# Pg09_1G_b.net
KiCad netlist of a schematic drawn in Altium Designer
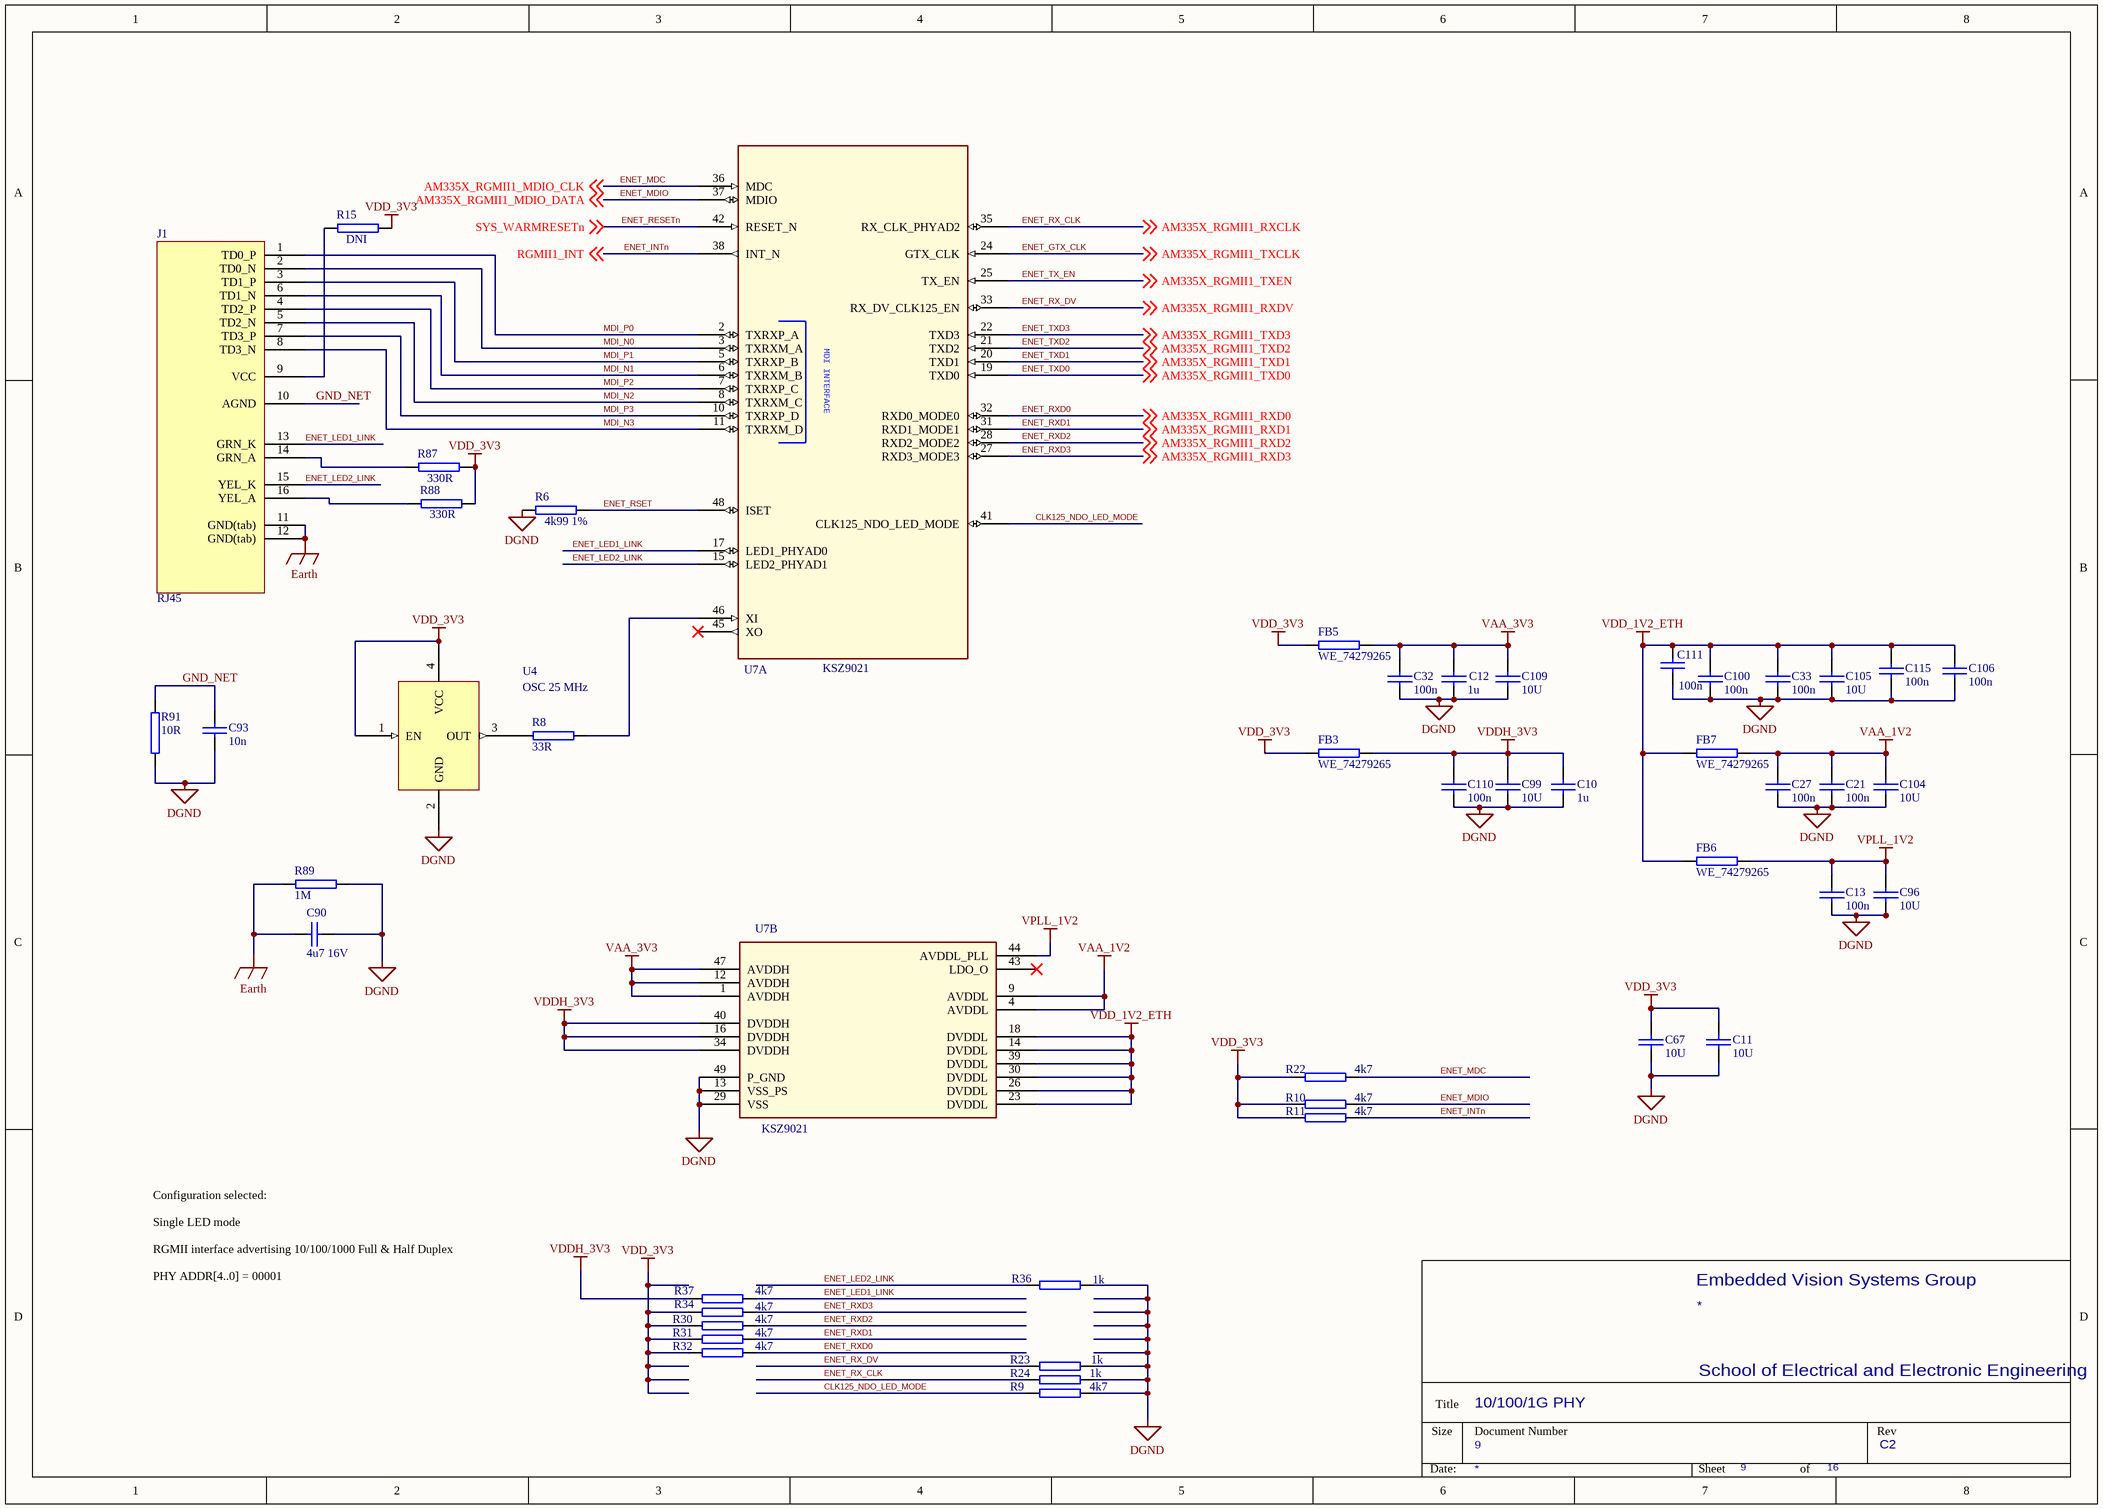
[diagram p0: Pg09_1G_b.SchDoc]

(export (version "E")
  (design (tool "Eeschema 10.0.6"))
  (components
    (comp (ref "C10")
      (value "1u")
      (footprint "0603")
      (description "NON-POLARISED CAP")
      (libsource (lib "Fireflash_B") (part "CAP"))
    )
    (comp (ref "C11")
      (value "10U")
      (footprint "0603")
      (description "NON-POLARISED CAP")
      (libsource (lib "ARMflash1_revC") (part "CAP"))
    )
    (comp (ref "C12")
      (value "1u")
      (footprint "0603")
      (description "NON-POLARISED CAP")
      (libsource (lib "ARMflash1_revC") (part "CAP"))
    )
    (comp (ref "C13")
      (value "100n")
      (footprint "SM-7351-CAP-0402")
      (description "NON-POLARISED CAP")
      (libsource (lib "ARMflash1_revC") (part "CAP"))
    )
    (comp (ref "C21")
      (value "100n")
      (footprint "SM-7351-CAP-0402")
      (description "NON-POLARISED CAP")
      (libsource (lib "ARMflash1_revC") (part "CAP"))
    )
    (comp (ref "C27")
      (value "100n")
      (footprint "SM-7351-CAP-0402")
      (description "NON-POLARISED CAP")
      (libsource (lib "ARMflash1_revC") (part "CAP"))
    )
    (comp (ref "C32")
      (value "100n")
      (footprint "0603")
      (description "NON-POLARISED CAP")
      (libsource (lib "ARMflash1_revC") (part "CAP"))
    )
    (comp (ref "C33")
      (value "100n")
      (footprint "sc0402")
      (description "NON-POLARISED CAP")
      (libsource (lib "ARMflash1_revC") (part "CAP"))
    )
    (comp (ref "C67")
      (value "10U")
      (footprint "0603")
      (description "NON-POLARISED CAP")
      (libsource (lib "ARMflash1_revC") (part "CAP"))
    )
    (comp (ref "C90")
      (value "4u7 16V")
      (footprint "0603")
      (description "NON-POLARISED CAP")
      (libsource (lib "ARMflash1_revC") (part "CAP"))
    )
    (comp (ref "C93")
      (value "10n")
      (footprint "0603")
      (description "NON-POLARISED CAP")
      (libsource (lib "ARMflash1_revC") (part "CAP"))
    )
    (comp (ref "C96")
      (value "10U")
      (footprint "0603")
      (description "NON-POLARISED CAP")
      (libsource (lib "ARMflash1_revC") (part "CAP"))
    )
    (comp (ref "C99")
      (value "10U")
      (footprint "0603")
      (description "NON-POLARISED CAP")
      (libsource (lib "ARMflash1_revC") (part "CAP"))
    )
    (comp (ref "C100")
      (value "100n")
      (footprint "SM-7351-CAP-0402")
      (description "NON-POLARISED CAP")
      (libsource (lib "ARMflash1_revC") (part "CAP"))
    )
    (comp (ref "C104")
      (value "10U")
      (footprint "0603")
      (description "NON-POLARISED CAP")
      (libsource (lib "ARMflash1_revC") (part "CAP"))
    )
    (comp (ref "C105")
      (value "10U")
      (footprint "0603")
      (description "NON-POLARISED CAP")
      (libsource (lib "ARMflash1_revC") (part "CAP"))
    )
    (comp (ref "C106")
      (value "100n")
      (footprint "0603")
      (description "NON-POLARISED CAP")
      (libsource (lib "Fireflash_B") (part "CAP"))
    )
    (comp (ref "C109")
      (value "10U")
      (footprint "0603")
      (description "NON-POLARISED CAP")
      (libsource (lib "ARMflash1_revC") (part "CAP"))
    )
    (comp (ref "C110")
      (value "100n")
      (footprint "0603")
      (description "NON-POLARISED CAP")
      (libsource (lib "ARMflash1_revC") (part "CAP"))
    )
    (comp (ref "C111")
      (value "100n")
      (footprint "0603")
      (description "NON-POLARISED CAP")
      (libsource (lib "ARMflash1_revC") (part "CAP"))
    )
    (comp (ref "C115")
      (value "100n")
      (footprint "SM-7351-CAP-0402")
      (description "NON-POLARISED CAP")
      (libsource (lib "ARMflash1_revC") (part "CAP"))
    )
    (comp (ref "FB3")
      (value "WE_74279265")
      (footprint "0603")
      (description "Wurth Eleckronik 0603 ferrite bead pn 74279265")
      (libsource (lib "Ibis4") (part "WE_74279265"))
    )
    (comp (ref "FB5")
      (value "WE_74279265")
      (footprint "0603")
      (description "Wurth Eleckronik 0603 ferrite bead pn 74279265")
      (libsource (lib "Ibis4") (part "WE_74279265"))
    )
    (comp (ref "FB6")
      (value "WE_74279265")
      (footprint "0603")
      (description "Wurth Eleckronik 0603 ferrite bead pn 74279265")
      (libsource (lib "Ibis4") (part "WE_74279265"))
    )
    (comp (ref "FB7")
      (value "WE_74279265")
      (footprint "0603")
      (description "Wurth Eleckronik 0603 ferrite bead pn 74279265")
      (libsource (lib "Ibis4") (part "WE_74279265"))
    )
    (comp (ref "J1")
      (value "RJ45")
      (footprint "RJ45_tripleSpeed")
      (description "RJ45 Mag Jack triple speed")
      (libsource (lib "ARMflash_mini_revB_rev") (part "WE_7499111121A RJ45 triple speed"))
    )
    (comp (ref "R6")
      (value "4k99 1%")
      (footprint "sc0402")
      (description "RESISTOR")
      (libsource (lib "Fireflash_B") (part "RES"))
    )
    (comp (ref "R8")
      (value "33R")
      (footprint "sc0402")
      (description "RESISTOR")
      (libsource (lib "Fireflash_B") (part "RES"))
    )
    (comp (ref "R9")
      (value "4k7")
      (footprint "sc0402")
      (description "RESISTOR")
      (libsource (lib "Fireflash_B") (part "RES"))
    )
    (comp (ref "R10")
      (value "4k7")
      (footprint "sc0402")
      (description "RESISTOR")
      (libsource (lib "Fireflash_B") (part "RES"))
    )
    (comp (ref "R11")
      (value "4k7")
      (footprint "sc0402")
      (description "RESISTOR")
      (libsource (lib "Fireflash_B") (part "RES"))
    )
    (comp (ref "R15")
      (value "DNI")
      (footprint "sc0402")
      (description "RESISTOR")
      (libsource (lib "Fireflash_B") (part "RES"))
    )
    (comp (ref "R22")
      (value "4k7")
      (footprint "sc0402")
      (description "RESISTOR")
      (libsource (lib "Fireflash_B") (part "RES"))
    )
    (comp (ref "R23")
      (value "1k")
      (footprint "sc0402")
      (description "RESISTOR")
      (libsource (lib "Fireflash_B") (part "RES"))
    )
    (comp (ref "R24")
      (value "1k")
      (footprint "sc0402")
      (description "RESISTOR")
      (libsource (lib "Fireflash_B") (part "RES"))
    )
    (comp (ref "R30")
      (value "4k7")
      (footprint "sc0402")
      (description "RESISTOR")
      (libsource (lib "Fireflash_B") (part "RES"))
    )
    (comp (ref "R31")
      (value "4k7")
      (footprint "sc0402")
      (description "RESISTOR")
      (libsource (lib "Fireflash_B") (part "RES"))
    )
    (comp (ref "R32")
      (value "4k7")
      (footprint "sc0402")
      (description "RESISTOR")
      (libsource (lib "Fireflash_B") (part "RES"))
    )
    (comp (ref "R34")
      (value "4k7")
      (footprint "sc0402")
      (description "RESISTOR")
      (libsource (lib "Fireflash_B") (part "RES"))
    )
    (comp (ref "R36")
      (value "1k")
      (footprint "sc0402")
      (description "RESISTOR")
      (libsource (lib "Fireflash_B") (part "RES"))
    )
    (comp (ref "R37")
      (value "4k7")
      (footprint "sc0402")
      (description "RESISTOR")
      (libsource (lib "Fireflash_B") (part "RES"))
    )
    (comp (ref "R87")
      (value "330R")
      (footprint "sc0402")
      (description "RESISTOR")
      (libsource (lib "Fireflash_B") (part "RES"))
    )
    (comp (ref "R88")
      (value "330R")
      (footprint "sc0402")
      (description "RESISTOR")
      (libsource (lib "Fireflash_B") (part "RES"))
    )
    (comp (ref "R89")
      (value "1M")
      (footprint "0603")
      (description "RESISTOR")
      (libsource (lib "Fireflash_B") (part "RES"))
    )
    (comp (ref "R91")
      (value "10R")
      (footprint "0603")
      (description "RESISTOR")
      (libsource (lib "Fireflash_B") (part "RES"))
    )
    (comp (ref "U4")
      (value "OSC 25 MHz")
      (footprint "Osc 3.2x2.5")
      (description "XTAL OSCILLATOR MODULE")
      (libsource (lib "ARMflash_mini") (part "OSC"))
    )
    (comp (ref "U7")
      (value "KSZ9021")
      (footprint "QFN48_0.5mmPitch")
      (libsource (lib "*") (part "KSZ9021RN_4"))
    )
  )
  (nets
    (net (code "1") (name "/CLK125_NDO_LED_MODE") (class "Default")
      (node (ref "R9") (pin "1") (pintype "passive"))
      (node (ref "U7") (pin "41") (pinfunction "CLK125_NDO_LED_MODE_41") (pintype "bidirectional"))
    )
    (net (code "2") (name "/ENET_LED1_LINK") (class "Default")
      (node (ref "J1") (pin "13") (pinfunction "GRN_K_13") (pintype "passive"))
      (node (ref "R37") (pin "2") (pintype "passive"))
      (node (ref "U7") (pin "17") (pinfunction "LED1_PHYAD0_17") (pintype "bidirectional"))
    )
    (net (code "3") (name "/ENET_LED2_LINK") (class "Default")
      (node (ref "J1") (pin "15") (pinfunction "YEL_K_15") (pintype "passive"))
      (node (ref "R36") (pin "1") (pintype "passive"))
      (node (ref "U7") (pin "15") (pinfunction "LED2_PHYAD1_15") (pintype "bidirectional"))
    )
    (net (code "4") (name "/ENET_RSET") (class "Default")
      (node (ref "R6") (pin "2") (pintype "passive"))
      (node (ref "U7") (pin "48") (pinfunction "ISET_48") (pintype "bidirectional"))
    )
    (net (code "5") (name "/GND_NET") (class "Default")
      (node (ref "C93") (pin "1") (pintype "passive"))
      (node (ref "J1") (pin "10") (pinfunction "AGND_10") (pintype "passive"))
      (node (ref "R91") (pin "2") (pintype "passive"))
    )
    (net (code "6") (name "/MDI_N0") (class "Default")
      (node (ref "J1") (pin "2") (pinfunction "TD0_N_2") (pintype "passive"))
      (node (ref "U7") (pin "3") (pinfunction "TXRXM_A_3") (pintype "bidirectional"))
    )
    (net (code "7") (name "/MDI_N1") (class "Default")
      (node (ref "J1") (pin "6") (pinfunction "TD1_N_6") (pintype "passive"))
      (node (ref "U7") (pin "6") (pinfunction "TXRXM_B_6") (pintype "bidirectional"))
    )
    (net (code "8") (name "/MDI_N2") (class "Default")
      (node (ref "J1") (pin "5") (pinfunction "TD2_N_5") (pintype "passive"))
      (node (ref "U7") (pin "8") (pinfunction "TXRXM_C_8") (pintype "bidirectional"))
    )
    (net (code "9") (name "/MDI_N3") (class "Default")
      (node (ref "J1") (pin "8") (pinfunction "TD3_N_8") (pintype "passive"))
      (node (ref "U7") (pin "11") (pinfunction "TXRXM_D_11") (pintype "bidirectional"))
    )
    (net (code "10") (name "/MDI_P0") (class "Default")
      (node (ref "J1") (pin "1") (pinfunction "TD0_P_1") (pintype "passive"))
      (node (ref "U7") (pin "2") (pinfunction "TXRXP_A_2") (pintype "bidirectional"))
    )
    (net (code "11") (name "/MDI_P1") (class "Default")
      (node (ref "J1") (pin "3") (pinfunction "TD1_P_3") (pintype "passive"))
      (node (ref "U7") (pin "5") (pinfunction "TXRXP_B_5") (pintype "bidirectional"))
    )
    (net (code "12") (name "/MDI_P2") (class "Default")
      (node (ref "J1") (pin "4") (pinfunction "TD2_P_4") (pintype "passive"))
      (node (ref "U7") (pin "7") (pinfunction "TXRXP_C_7") (pintype "bidirectional"))
    )
    (net (code "13") (name "/MDI_P3") (class "Default")
      (node (ref "J1") (pin "7") (pinfunction "TD3_P_7") (pintype "passive"))
      (node (ref "U7") (pin "10") (pinfunction "TXRXP_D_10") (pintype "bidirectional"))
    )
    (net (code "14") (name "AM335X_RGMII1_MDIO_CLK") (class "Default")
      (node (ref "R22") (pin "2") (pintype "passive"))
      (node (ref "U7") (pin "36") (pinfunction "MDC_36") (pintype "input"))
    )
    (net (code "15") (name "AM335X_RGMII1_MDIO_DATA") (class "Default")
      (node (ref "R10") (pin "2") (pintype "passive"))
      (node (ref "U7") (pin "37") (pinfunction "MDIO_37") (pintype "bidirectional"))
    )
    (net (code "16") (name "AM335X_RGMII1_RXCLK") (class "Default")
      (node (ref "R24") (pin "1") (pintype "passive"))
      (node (ref "U7") (pin "35") (pinfunction "RX_CLK_PHYAD2_35") (pintype "bidirectional"))
    )
    (net (code "17") (name "AM335X_RGMII1_RXD0") (class "Default")
      (node (ref "R32") (pin "2") (pintype "passive"))
      (node (ref "U7") (pin "32") (pinfunction "RXD0_MODE0_32") (pintype "bidirectional"))
    )
    (net (code "18") (name "AM335X_RGMII1_RXD1") (class "Default")
      (node (ref "R31") (pin "2") (pintype "passive"))
      (node (ref "U7") (pin "31") (pinfunction "RXD1_MODE1_31") (pintype "bidirectional"))
    )
    (net (code "19") (name "AM335X_RGMII1_RXD2") (class "Default")
      (node (ref "R30") (pin "2") (pintype "passive"))
      (node (ref "U7") (pin "28") (pinfunction "RXD2_MODE2_28") (pintype "bidirectional"))
    )
    (net (code "20") (name "AM335X_RGMII1_RXD3") (class "Default")
      (node (ref "R34") (pin "2") (pintype "passive"))
      (node (ref "U7") (pin "27") (pinfunction "RXD3_MODE3_27") (pintype "bidirectional"))
    )
    (net (code "21") (name "AM335X_RGMII1_RXDV") (class "Default")
      (node (ref "R23") (pin "1") (pintype "passive"))
      (node (ref "U7") (pin "33") (pinfunction "RX_DV_CLK125_EN_33") (pintype "bidirectional"))
    )
    (net (code "22") (name "AM335X_RGMII1_TXCLK") (class "Default")
      (node (ref "U7") (pin "24") (pinfunction "GTX_CLK_24") (pintype "input"))
    )
    (net (code "23") (name "AM335X_RGMII1_TXD0") (class "Default")
      (node (ref "U7") (pin "19") (pinfunction "TXD0_19") (pintype "input"))
    )
    (net (code "24") (name "AM335X_RGMII1_TXD1") (class "Default")
      (node (ref "U7") (pin "20") (pinfunction "TXD1_20") (pintype "input"))
    )
    (net (code "25") (name "AM335X_RGMII1_TXD2") (class "Default")
      (node (ref "U7") (pin "21") (pinfunction "TXD2_21") (pintype "input"))
    )
    (net (code "26") (name "AM335X_RGMII1_TXD3") (class "Default")
      (node (ref "U7") (pin "22") (pinfunction "TXD3_22") (pintype "input"))
    )
    (net (code "27") (name "AM335X_RGMII1_TXEN") (class "Default")
      (node (ref "U7") (pin "25") (pinfunction "TX_EN_25") (pintype "input"))
    )
    (net (code "28") (name "DGND") (class "Default")
      (node (ref "C10") (pin "2") (pintype "passive"))
      (node (ref "C100") (pin "2") (pintype "passive"))
      (node (ref "C104") (pin "2") (pintype "passive"))
      (node (ref "C105") (pin "2") (pintype "passive"))
      (node (ref "C106") (pin "2") (pintype "passive"))
      (node (ref "C109") (pin "2") (pintype "passive"))
      (node (ref "C11") (pin "2") (pintype "passive"))
      (node (ref "C110") (pin "2") (pintype "passive"))
      (node (ref "C111") (pin "2") (pintype "passive"))
      (node (ref "C115") (pin "2") (pintype "passive"))
      (node (ref "C12") (pin "2") (pintype "passive"))
      (node (ref "C13") (pin "2") (pintype "passive"))
      (node (ref "C21") (pin "2") (pintype "passive"))
      (node (ref "C27") (pin "2") (pintype "passive"))
      (node (ref "C32") (pin "2") (pintype "passive"))
      (node (ref "C33") (pin "2") (pintype "passive"))
      (node (ref "C67") (pin "2") (pintype "passive"))
      (node (ref "C90") (pin "2") (pintype "passive"))
      (node (ref "C93") (pin "2") (pintype "passive"))
      (node (ref "C96") (pin "2") (pintype "passive"))
      (node (ref "C99") (pin "2") (pintype "passive"))
      (node (ref "R23") (pin "2") (pintype "passive"))
      (node (ref "R24") (pin "2") (pintype "passive"))
      (node (ref "R36") (pin "2") (pintype "passive"))
      (node (ref "R6") (pin "1") (pintype "passive"))
      (node (ref "R89") (pin "1") (pintype "passive"))
      (node (ref "R9") (pin "2") (pintype "passive"))
      (node (ref "R91") (pin "1") (pintype "passive"))
      (node (ref "U4") (pin "2") (pinfunction "GND_2") (pintype "power_in"))
      (node (ref "U7") (pin "13") (pinfunction "VSS_PS_13") (pintype "power_in"))
      (node (ref "U7") (pin "29") (pinfunction "VSS_29") (pintype "power_in"))
      (node (ref "U7") (pin "49") (pinfunction "P_GND_49") (pintype "power_in"))
    )
    (net (code "29") (name "Earth") (class "Default")
      (node (ref "C90") (pin "1") (pintype "passive"))
      (node (ref "J1") (pin "11") (pinfunction "GND(tab)_11") (pintype "passive"))
      (node (ref "J1") (pin "12") (pinfunction "GND(tab)_12") (pintype "passive"))
      (node (ref "R89") (pin "2") (pintype "passive"))
    )
    (net (code "30") (name "Net-(J1-GRN_A)") (class "Default")
      (node (ref "J1") (pin "14") (pinfunction "GRN_A_14") (pintype "passive"))
      (node (ref "R87") (pin "1") (pintype "passive"))
    )
    (net (code "31") (name "Net-(J1-VCC)") (class "Default")
      (node (ref "J1") (pin "9") (pinfunction "VCC_9") (pintype "passive"))
      (node (ref "R15") (pin "1") (pintype "passive"))
    )
    (net (code "32") (name "Net-(J1-YEL_A)") (class "Default")
      (node (ref "J1") (pin "16") (pinfunction "YEL_A_16") (pintype "passive"))
      (node (ref "R88") (pin "1") (pintype "passive"))
    )
    (net (code "33") (name "Net-(U4-OUT)") (class "Default")
      (node (ref "R8") (pin "1") (pintype "passive"))
      (node (ref "U4") (pin "3") (pinfunction "OUT_3") (pintype "output"))
    )
    (net (code "34") (name "Net-(U7A-XI)") (class "Default")
      (node (ref "R8") (pin "2") (pintype "passive"))
      (node (ref "U7") (pin "46") (pinfunction "XI_46") (pintype "input"))
    )
    (net (code "35") (name "RGMII1_INT") (class "Default")
      (node (ref "R11") (pin "2") (pintype "passive"))
      (node (ref "U7") (pin "38") (pinfunction "INT_N_38") (pintype "output"))
    )
    (net (code "36") (name "SYS_WARMRESETn") (class "Default")
      (node (ref "U7") (pin "42") (pinfunction "RESET_N_42") (pintype "input"))
    )
    (net (code "37") (name "VAA_1V2") (class "Default")
      (node (ref "C104") (pin "1") (pintype "passive"))
      (node (ref "C21") (pin "1") (pintype "passive"))
      (node (ref "C27") (pin "1") (pintype "passive"))
      (node (ref "FB7") (pin "2") (pintype "passive"))
      (node (ref "U7") (pin "4") (pinfunction "AVDDL_4") (pintype "power_in"))
      (node (ref "U7") (pin "9") (pinfunction "AVDDL_9") (pintype "power_in"))
    )
    (net (code "38") (name "VAA_3V3") (class "Default")
      (node (ref "C109") (pin "1") (pintype "passive"))
      (node (ref "C12") (pin "1") (pintype "passive"))
      (node (ref "C32") (pin "1") (pintype "passive"))
      (node (ref "FB5") (pin "2") (pintype "passive"))
      (node (ref "U7") (pin "1") (pinfunction "AVDDH_1") (pintype "power_in"))
      (node (ref "U7") (pin "12") (pinfunction "AVDDH_12") (pintype "power_in"))
      (node (ref "U7") (pin "47") (pinfunction "AVDDH_47") (pintype "power_in"))
    )
    (net (code "39") (name "VDDH_3V3") (class "Default")
      (node (ref "C10") (pin "1") (pintype "passive"))
      (node (ref "C110") (pin "1") (pintype "passive"))
      (node (ref "C99") (pin "1") (pintype "passive"))
      (node (ref "FB3") (pin "2") (pintype "passive"))
      (node (ref "R37") (pin "1") (pintype "passive"))
      (node (ref "U7") (pin "16") (pinfunction "DVDDH_16") (pintype "power_in"))
      (node (ref "U7") (pin "34") (pinfunction "DVDDH_34") (pintype "power_in"))
      (node (ref "U7") (pin "40") (pinfunction "DVDDH_40") (pintype "power_in"))
    )
    (net (code "40") (name "VDD_1V2_ETH") (class "Default")
      (node (ref "C100") (pin "1") (pintype "passive"))
      (node (ref "C105") (pin "1") (pintype "passive"))
      (node (ref "C106") (pin "1") (pintype "passive"))
      (node (ref "C111") (pin "1") (pintype "passive"))
      (node (ref "C115") (pin "1") (pintype "passive"))
      (node (ref "C33") (pin "1") (pintype "passive"))
      (node (ref "FB6") (pin "1") (pintype "passive"))
      (node (ref "FB7") (pin "1") (pintype "passive"))
      (node (ref "U7") (pin "14") (pinfunction "DVDDL_14") (pintype "power_in"))
      (node (ref "U7") (pin "18") (pinfunction "DVDDL_18") (pintype "power_in"))
      (node (ref "U7") (pin "23") (pinfunction "DVDDL_23") (pintype "power_in"))
      (node (ref "U7") (pin "26") (pinfunction "DVDDL_26") (pintype "power_in"))
      (node (ref "U7") (pin "30") (pinfunction "DVDDL_30") (pintype "power_in"))
      (node (ref "U7") (pin "39") (pinfunction "DVDDL_39") (pintype "power_in"))
    )
    (net (code "41") (name "VDD_3V3") (class "Default")
      (node (ref "C11") (pin "1") (pintype "passive"))
      (node (ref "C67") (pin "1") (pintype "passive"))
      (node (ref "FB3") (pin "1") (pintype "passive"))
      (node (ref "FB5") (pin "1") (pintype "passive"))
      (node (ref "R10") (pin "1") (pintype "passive"))
      (node (ref "R11") (pin "1") (pintype "passive"))
      (node (ref "R15") (pin "2") (pintype "passive"))
      (node (ref "R22") (pin "1") (pintype "passive"))
      (node (ref "R30") (pin "1") (pintype "passive"))
      (node (ref "R31") (pin "1") (pintype "passive"))
      (node (ref "R32") (pin "1") (pintype "passive"))
      (node (ref "R34") (pin "1") (pintype "passive"))
      (node (ref "R87") (pin "2") (pintype "passive"))
      (node (ref "R88") (pin "2") (pintype "passive"))
      (node (ref "U4") (pin "1") (pinfunction "EN_1") (pintype "input"))
      (node (ref "U4") (pin "4") (pinfunction "VCC_4") (pintype "power_in"))
    )
    (net (code "42") (name "VPLL_1V2") (class "Default")
      (node (ref "C13") (pin "1") (pintype "passive"))
      (node (ref "C96") (pin "1") (pintype "passive"))
      (node (ref "FB6") (pin "2") (pintype "passive"))
      (node (ref "U7") (pin "44") (pinfunction "AVDDL_PLL_44") (pintype "power_in"))
    )
    (net (code "43") (name "unconnected-(U7A-XO-Pad45)") (class "Default")
      (node (ref "U7") (pin "45") (pinfunction "XO_45") (pintype "output+no_connect"))
    )
    (net (code "44") (name "unconnected-(U7B-LDO_O-Pad43)") (class "Default")
      (node (ref "U7") (pin "43") (pinfunction "LDO_O_43") (pintype "power_in+no_connect"))
    )
  )
)
